# TSOC_GROVEY_FOUR.net
KiCad netlist of a schematic drawn in EAGLE
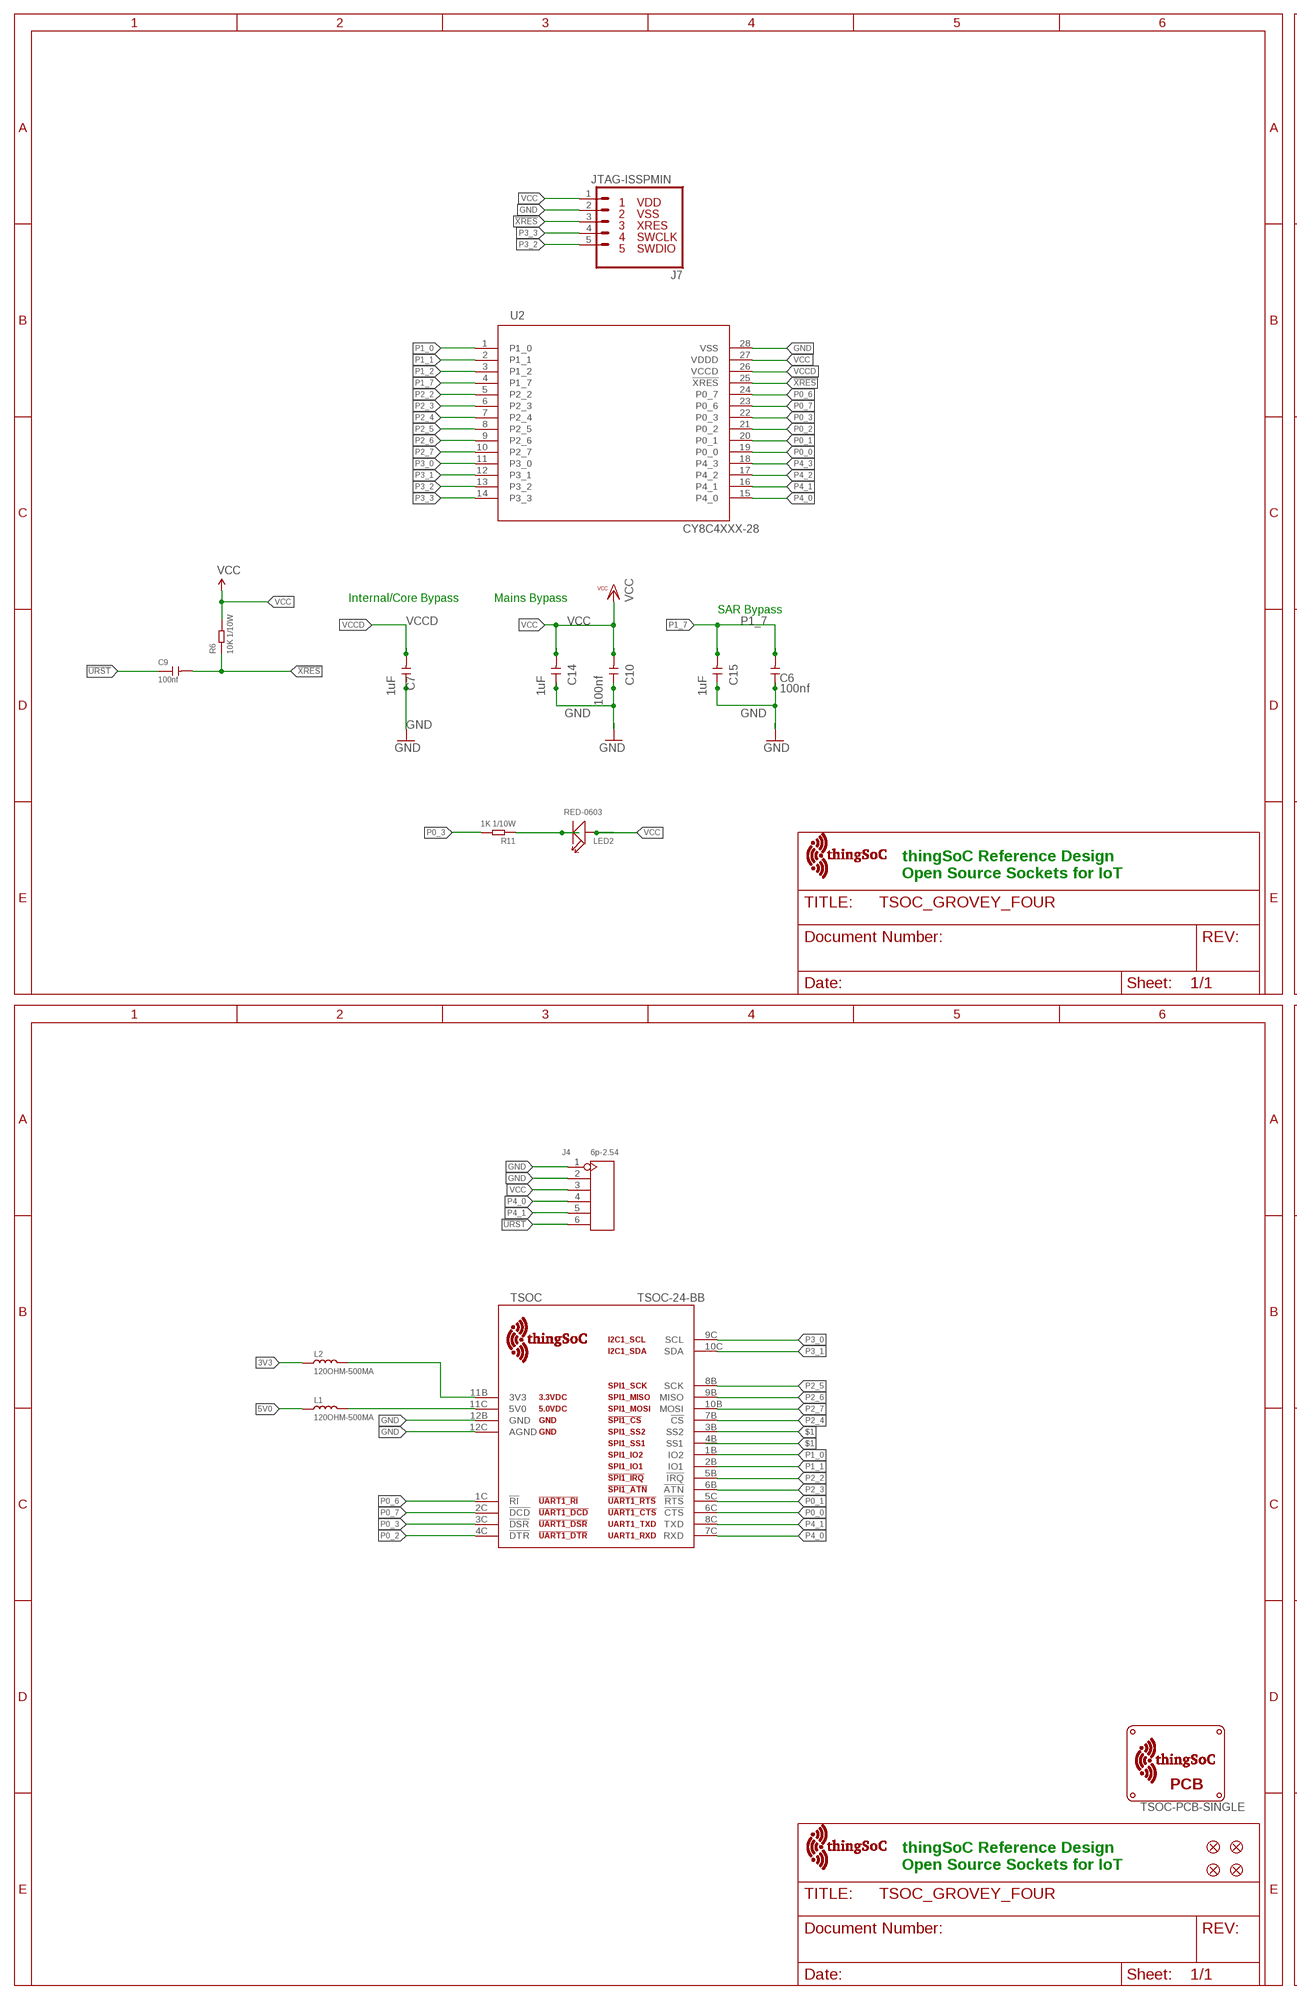
[diagram p0: schematic, sheet 1, part 1 of 2]
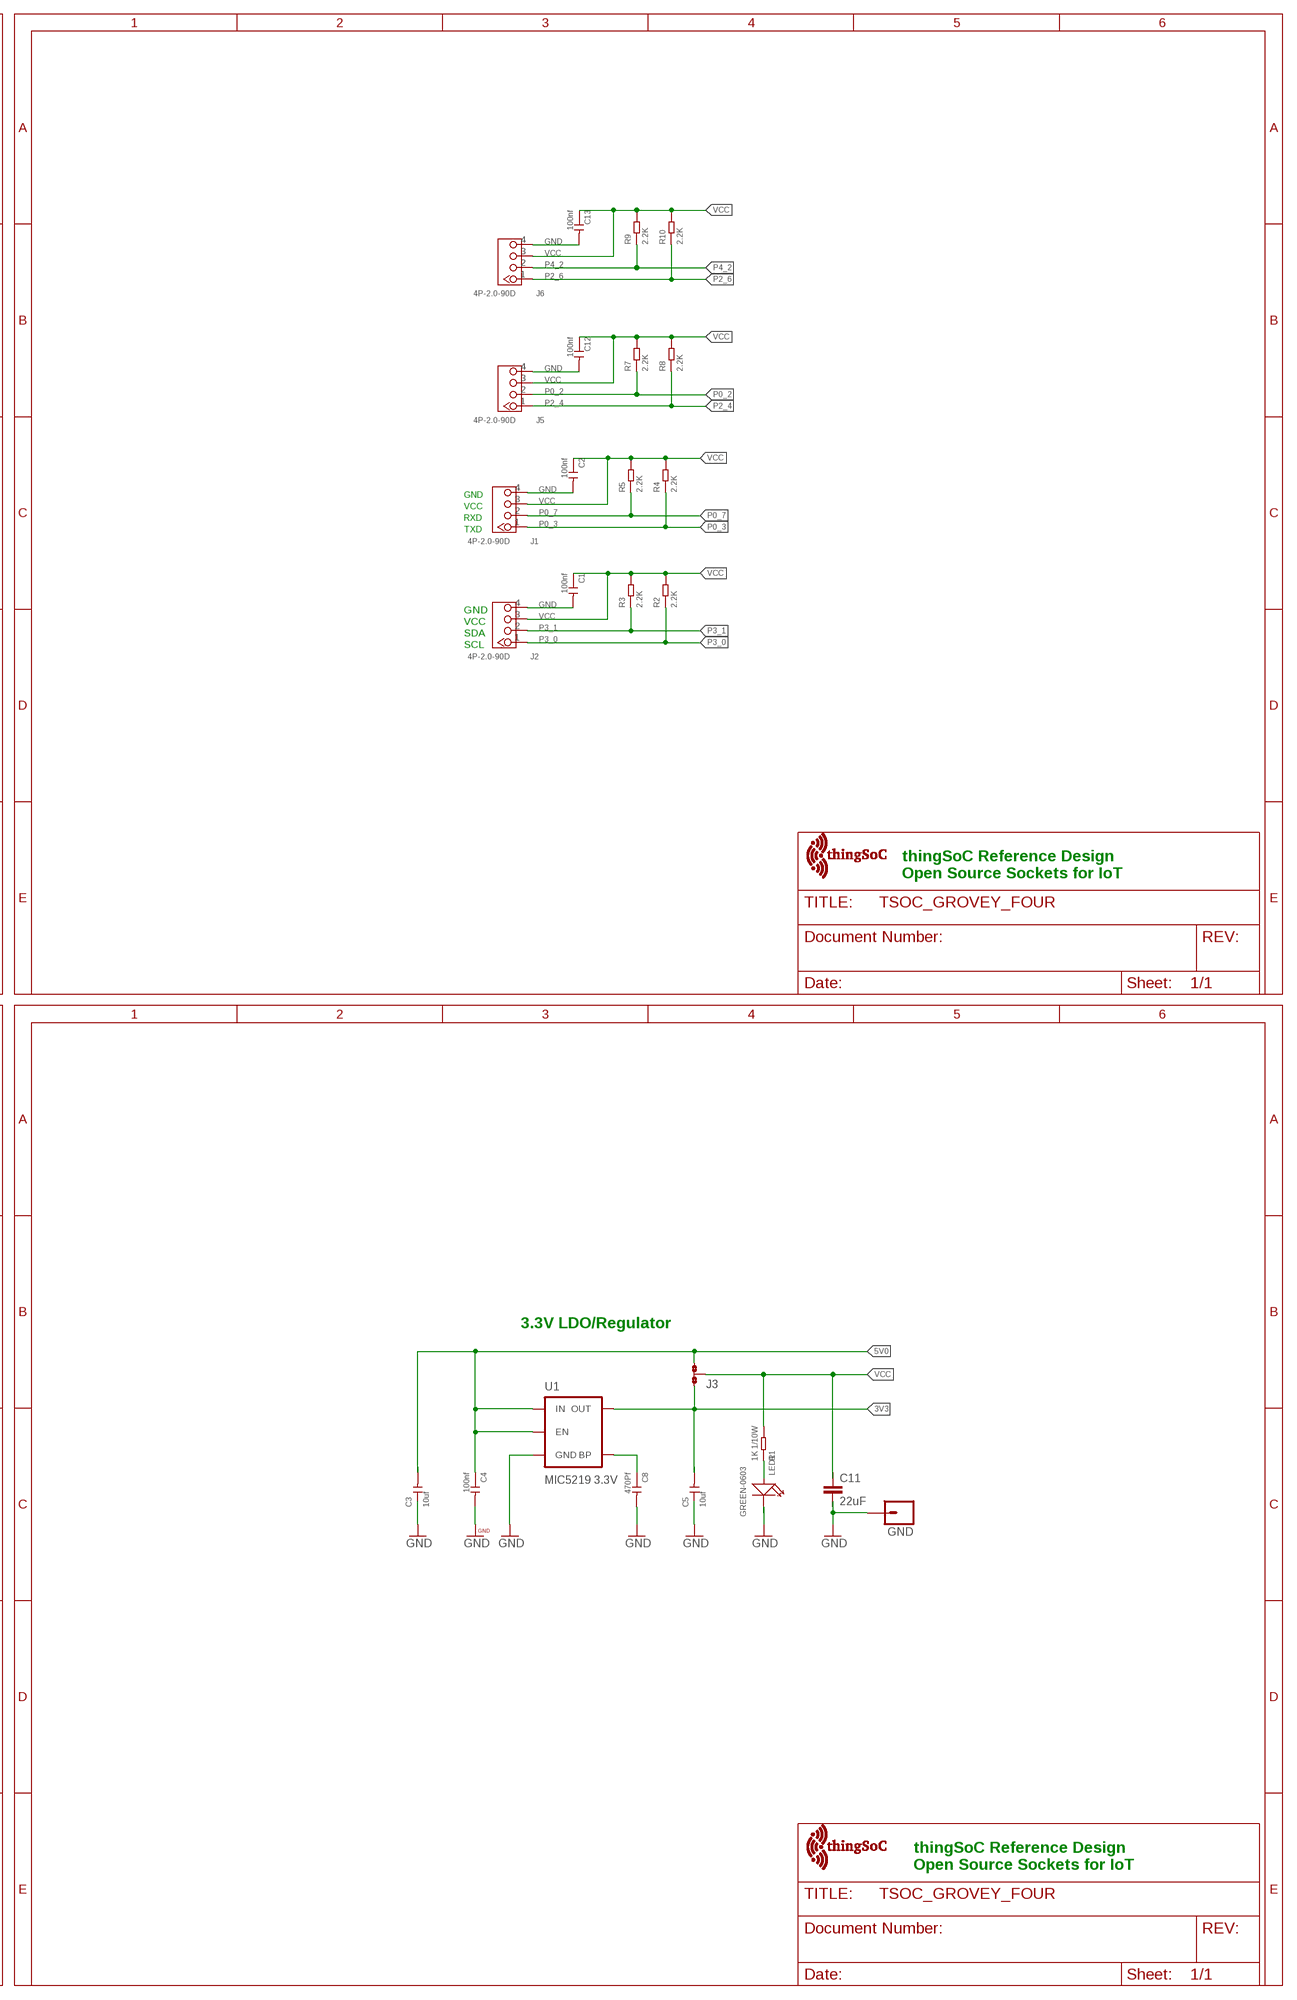
[diagram p1: schematic, sheet 1, part 2 of 2]

(export (version "E")
  (design (tool "Eeschema 10.0.6"))
  (components
    (comp (ref "$$U$1")
      (value "TSOC-PCB-SINGLE")
      (footprint "eagle-import:TSOC-BB-BRD-DIM")
      (libsource (lib "eagle-import") (part "TSOC-PCB-SINGLE"))
    )
    (comp (ref "C1")
      (value "100nf")
      (footprint "eagle-import:C0603")
      (fields (field (name "MPN") "CC0603KRX7R9BB104"))
      (libsource (lib "eagle-import") (part "CERAMIC-100NF-50V-10%-X7R(0603)"))
    )
    (comp (ref "C2")
      (value "100nf")
      (footprint "eagle-import:C0603")
      (fields (field (name "MPN") "CC0603KRX7R9BB104"))
      (libsource (lib "eagle-import") (part "CERAMIC-100NF-50V-10%-X7R(0603)"))
    )
    (comp (ref "C3")
      (value "10uf")
      (footprint "eagle-import:C0603")
      (fields (field (name "MPN") "CC0603KRX5R6BB106"))
      (libsource (lib "eagle-import") (part "CERAMIC-10UF-10V-10%-X5R(0603)"))
    )
    (comp (ref "C4")
      (value "100nf")
      (footprint "eagle-import:C0603")
      (fields (field (name "MPN") "CC0603KRX7R9BB104"))
      (libsource (lib "eagle-import") (part "CERAMIC-100NF-50V-10%-X7R(0603)"))
    )
    (comp (ref "C5")
      (value "10uf")
      (footprint "eagle-import:C0603")
      (fields (field (name "MPN") "CC0603KRX5R6BB106"))
      (libsource (lib "eagle-import") (part "CERAMIC-10UF-10V-10%-X5R(0603)"))
    )
    (comp (ref "C6")
      (value "100nf")
      (footprint "eagle-import:C0603")
      (fields (field (name "MPN") "CC0603KRX7R9BB104"))
      (libsource (lib "eagle-import") (part "CERAMIC-100NF-50V-10%-X7R(0603)"))
    )
    (comp (ref "C7")
      (value "1uF")
      (footprint "eagle-import:C0603")
      (fields (field (name "MPN") "CC0603KRX7R9BB104"))
      (libsource (lib "eagle-import") (part "CERAMIC-100NF-50V-10%-X7R(0603)"))
    )
    (comp (ref "C8")
      (value "470Pf")
      (footprint "eagle-import:C0603")
      (fields (field (name "MPN") "CC0603KRX7R9BB104"))
      (libsource (lib "eagle-import") (part "CERAMIC-100NF-50V-10%-X7R(0603)"))
    )
    (comp (ref "C9")
      (value "100nf")
      (footprint "eagle-import:C0603")
      (fields (field (name "MPN") "CC0603KRX7R9BB104"))
      (libsource (lib "eagle-import") (part "CERAMIC-100NF-50V-10%-X7R(0603)"))
    )
    (comp (ref "C10")
      (value "100nf")
      (footprint "eagle-import:C0603")
      (fields (field (name "MPN") "CC0603KRX7R9BB104"))
      (libsource (lib "eagle-import") (part "CERAMIC-100NF-50V-10%-X7R(0603)"))
    )
    (comp (ref "C11")
      (value "22uF")
      (footprint "eagle-import:EIA-1206")
      (libsource (lib "eagle-import") (part "CAP-1206"))
    )
    (comp (ref "C12")
      (value "100nf")
      (footprint "eagle-import:C0603")
      (fields (field (name "MPN") "CC0603KRX7R9BB104"))
      (libsource (lib "eagle-import") (part "CERAMIC-100NF-50V-10%-X7R(0603)"))
    )
    (comp (ref "C13")
      (value "100nf")
      (footprint "eagle-import:C0603")
      (fields (field (name "MPN") "CC0603KRX7R9BB104"))
      (libsource (lib "eagle-import") (part "CERAMIC-100NF-50V-10%-X7R(0603)"))
    )
    (comp (ref "C14")
      (value "1uF")
      (footprint "eagle-import:C0603")
      (fields (field (name "MPN") "CC0603KRX7R9BB104"))
      (libsource (lib "eagle-import") (part "CERAMIC-100NF-50V-10%-X7R(0603)"))
    )
    (comp (ref "C15")
      (value "1uF")
      (footprint "eagle-import:C0603")
      (fields (field (name "MPN") "CC0603KRX7R9BB104"))
      (libsource (lib "eagle-import") (part "CERAMIC-100NF-50V-10%-X7R(0603)"))
    )
    (comp (ref "FID1")
      (value "FIDUCIALUFIDUCIAL")
      (footprint "eagle-import:MICRO-FIDUCIAL")
      (libsource (lib "eagle-import") (part "FIDUCIALUFIDUCIAL"))
    )
    (comp (ref "FID2")
      (value "FIDUCIALUFIDUCIAL")
      (footprint "eagle-import:MICRO-FIDUCIAL")
      (libsource (lib "eagle-import") (part "FIDUCIALUFIDUCIAL"))
    )
    (comp (ref "FID3")
      (value "FIDUCIALUFIDUCIAL")
      (footprint "eagle-import:MICRO-FIDUCIAL")
      (libsource (lib "eagle-import") (part "FIDUCIALUFIDUCIAL"))
    )
    (comp (ref "FID4")
      (value "FIDUCIALUFIDUCIAL")
      (footprint "eagle-import:MICRO-FIDUCIAL")
      (libsource (lib "eagle-import") (part "FIDUCIALUFIDUCIAL"))
    )
    (comp (ref "GND")
      (value "M01PTH")
      (footprint "eagle-import:1X01")
      (libsource (lib "eagle-import") (part "M01PTH"))
    )
    (comp (ref "J1")
      (value "4P-2.0-90D")
      (footprint "eagle-import:HW4-2.0-90D")
      (libsource (lib "eagle-import") (part "GROVE-CONNECTOR-DIP-90D(4P-2.0)"))
    )
    (comp (ref "J2")
      (value "4P-2.0-90D")
      (footprint "eagle-import:HW4-2.0-90D")
      (libsource (lib "eagle-import") (part "GROVE-CONNECTOR-DIP-90D(4P-2.0)"))
    )
    (comp (ref "J3")
      (value "NO")
      (footprint "eagle-import:JMP-3-NO-PTH-2.54")
      (libsource (lib "eagle-import") (part "JMP-3-NO-PTH"))
    )
    (comp (ref "J4")
      (value "6p-2.54")
      (footprint "eagle-import:H6-2.54")
      (fields (field (name "MPN") "P125-1106A1BS116A1"))
      (libsource (lib "eagle-import") (part "DIP-BLACK-MALE-HEADER(6P-2.54)"))
    )
    (comp (ref "J5")
      (value "4P-2.0-90D")
      (footprint "eagle-import:HW4-2.0-90D")
      (libsource (lib "eagle-import") (part "GROVE-CONNECTOR-DIP-90D(4P-2.0)"))
    )
    (comp (ref "J6")
      (value "4P-2.0-90D")
      (footprint "eagle-import:HW4-2.0-90D")
      (libsource (lib "eagle-import") (part "GROVE-CONNECTOR-DIP-90D(4P-2.0)"))
    )
    (comp (ref "J7")
      (value "JTAG-ISSPMIN")
      (footprint "eagle-import:PSOC_JTAG_MINSILK")
      (libsource (lib "eagle-import") (part "JTAG-ISSPMIN"))
    )
    (comp (ref "L1")
      (value "120OHM-500MA")
      (footprint "eagle-import:L0603")
      (fields (field (name "MPN") "BLM18AG121SN1D"))
      (libsource (lib "eagle-import") (part "SMD-FERRITE-CHIP-120-OHM-500MA(0603)"))
    )
    (comp (ref "L2")
      (value "120OHM-500MA")
      (footprint "eagle-import:L0603")
      (fields (field (name "MPN") "BLM18AG121SN1D"))
      (libsource (lib "eagle-import") (part "SMD-FERRITE-CHIP-120-OHM-500MA(0603)"))
    )
    (comp (ref "LED1")
      (value "GREEN-0603")
      (footprint "eagle-import:LED-0603")
      (fields (field (name "MPN") "19-217-G7C-AN1P2-3T"))
      (libsource (lib "eagle-import") (part "SMD-LED-CLEAR-GREEN(0603)"))
    )
    (comp (ref "LED2")
      (value "RED-0603")
      (footprint "eagle-import:LED-0603")
      (fields (field (name "MPN") "19-217-G7C-AN1P2-3T"))
      (libsource (lib "eagle-import") (part "SMD-LED-CLEAR-GREEN(0603)"))
    )
    (comp (ref "R1")
      (value "1K 1/10W")
      (footprint "eagle-import:R0603")
      (fields (field (name "MPN") "RC0603JR-071KL"))
      (libsource (lib "eagle-import") (part "SMD-RES-1K-5%-1/10W(0603)"))
    )
    (comp (ref "R2")
      (value "2.2K")
      (footprint "eagle-import:R0603")
      (fields (field (name "MPN") "RC0603JR-072K2L"))
      (libsource (lib "eagle-import") (part "SMD-RES-2.2K-5%-1/10W(0603)"))
    )
    (comp (ref "R3")
      (value "2.2K")
      (footprint "eagle-import:R0603")
      (fields (field (name "MPN") "RC0603JR-072K2L"))
      (libsource (lib "eagle-import") (part "SMD-RES-2.2K-5%-1/10W(0603)"))
    )
    (comp (ref "R4")
      (value "2.2K")
      (footprint "eagle-import:R0603")
      (fields (field (name "MPN") "RC0603JR-072K2L"))
      (libsource (lib "eagle-import") (part "SMD-RES-2.2K-5%-1/10W(0603)"))
    )
    (comp (ref "R5")
      (value "2.2K")
      (footprint "eagle-import:R0603")
      (fields (field (name "MPN") "RC0603JR-072K2L"))
      (libsource (lib "eagle-import") (part "SMD-RES-2.2K-5%-1/10W(0603)"))
    )
    (comp (ref "R6")
      (value "10K 1/10W")
      (footprint "eagle-import:R0603")
      (fields (field (name "MPN") "RC0603JR-0710KL"))
      (libsource (lib "eagle-import") (part "SMD-RES-10K-5%-1/10W(0603)"))
    )
    (comp (ref "R7")
      (value "2.2K")
      (footprint "eagle-import:R0603")
      (fields (field (name "MPN") "RC0603JR-072K2L"))
      (libsource (lib "eagle-import") (part "SMD-RES-2.2K-5%-1/10W(0603)"))
    )
    (comp (ref "R8")
      (value "2.2K")
      (footprint "eagle-import:R0603")
      (fields (field (name "MPN") "RC0603JR-072K2L"))
      (libsource (lib "eagle-import") (part "SMD-RES-2.2K-5%-1/10W(0603)"))
    )
    (comp (ref "R9")
      (value "2.2K")
      (footprint "eagle-import:R0603")
      (fields (field (name "MPN") "RC0603JR-072K2L"))
      (libsource (lib "eagle-import") (part "SMD-RES-2.2K-5%-1/10W(0603)"))
    )
    (comp (ref "R10")
      (value "2.2K")
      (footprint "eagle-import:R0603")
      (fields (field (name "MPN") "RC0603JR-072K2L"))
      (libsource (lib "eagle-import") (part "SMD-RES-2.2K-5%-1/10W(0603)"))
    )
    (comp (ref "R11")
      (value "1K 1/10W")
      (footprint "eagle-import:R0603")
      (fields (field (name "MPN") "RC0603JR-071KL"))
      (libsource (lib "eagle-import") (part "SMD-RES-1K-5%-1/10W(0603)"))
    )
    (comp (ref "TSOC")
      (value "TSOC-24-BB")
      (footprint "eagle-import:TSOC-BB-S24")
      (libsource (lib "eagle-import") (part "TSOC-24-BB"))
    )
    (comp (ref "U$1")
      (value "TSOC-LOGO-SMALL")
      (footprint "eagle-import:TSOC-LOGO-SML")
      (libsource (lib "eagle-import") (part "TSOC-LOGO-SMALL"))
    )
    (comp (ref "U$101")
      (value "TSOC-LOGO-SMALL")
      (footprint "eagle-import:TSOC-LOGO-SML")
      (libsource (lib "eagle-import") (part "TSOC-LOGO-SMALL"))
    )
    (comp (ref "U$102")
      (value "TSOC-LOGO-LRG")
      (footprint "eagle-import:TSOC-LOGO-LRG")
      (libsource (lib "eagle-import") (part "TSOC-LOGO-LRG"))
    )
    (comp (ref "U$103")
      (value "TSOC-LOGO-SMALL")
      (footprint "eagle-import:TSOC-LOGO-SML")
      (libsource (lib "eagle-import") (part "TSOC-LOGO-SMALL"))
    )
    (comp (ref "U1")
      (value "MIC5219 3.3V")
      (footprint "eagle-import:SOT23-5")
      (libsource (lib "eagle-import") (part "V_REG_MIC52193.3V"))
    )
    (comp (ref "U2")
      (value "CY8C4XXX-28")
      (footprint "eagle-import:SSOP28")
      (libsource (lib "eagle-import") (part "CY8C4XXX-28"))
    )
  )
  (nets
    (net (code "1") (name "$1") (class "Default")
      (node (ref "TSOC") (pin "3B") (pinfunction "SS2_3B") (pintype "bidirectional"))
      (node (ref "TSOC") (pin "4B") (pinfunction "SS1_4B") (pintype "bidirectional"))
    )
    (net (code "2") (name "/~{URST}") (class "Default")
      (node (ref "C9") (pin "1") (pinfunction "1_1") (pintype "passive"))
      (node (ref "J4") (pin "6") (pinfunction "6_6") (pintype "bidirectional"))
    )
    (net (code "3") (name "/~{XRES}") (class "Default")
      (node (ref "C9") (pin "2") (pinfunction "2_2") (pintype "passive"))
      (node (ref "J7") (pin "3") (pinfunction "3_3") (pintype "passive"))
      (node (ref "R6") (pin "1") (pinfunction "1_1") (pintype "passive"))
      (node (ref "U2") (pin "25") (pinfunction "~{XRES}_25") (pintype "bidirectional"))
    )
    (net (code "4") (name "3V3") (class "Default")
      (node (ref "C5") (pin "2") (pinfunction "2_2") (pintype "passive"))
      (node (ref "J3") (pin "1") (pinfunction "1_1") (pintype "passive"))
      (node (ref "L2") (pin "1") (pinfunction "1_1") (pintype "passive"))
      (node (ref "U1") (pin "5") (pinfunction "OUT_5") (pintype "passive"))
    )
    (net (code "5") (name "5V0") (class "Default")
      (node (ref "C3") (pin "2") (pinfunction "2_2") (pintype "passive"))
      (node (ref "C4") (pin "1") (pinfunction "1_1") (pintype "passive"))
      (node (ref "J3") (pin "3") (pinfunction "3_3") (pintype "passive"))
      (node (ref "L1") (pin "1") (pinfunction "1_1") (pintype "passive"))
      (node (ref "U1") (pin "1") (pinfunction "IN_1") (pintype "input"))
      (node (ref "U1") (pin "3") (pinfunction "EN_3") (pintype "input"))
    )
    (net (code "6") (name "GND") (class "Default")
      (node (ref "C1") (pin "2") (pinfunction "2_2") (pintype "passive"))
      (node (ref "C10") (pin "1") (pinfunction "1_1") (pintype "passive"))
      (node (ref "C11") (pin "2") (pinfunction "2_2") (pintype "passive"))
      (node (ref "C12") (pin "2") (pinfunction "2_2") (pintype "passive"))
      (node (ref "C13") (pin "2") (pinfunction "2_2") (pintype "passive"))
      (node (ref "C14") (pin "1") (pinfunction "1_1") (pintype "passive"))
      (node (ref "C15") (pin "1") (pinfunction "1_1") (pintype "passive"))
      (node (ref "C2") (pin "2") (pinfunction "2_2") (pintype "passive"))
      (node (ref "C3") (pin "1") (pinfunction "1_1") (pintype "passive"))
      (node (ref "C4") (pin "2") (pinfunction "2_2") (pintype "passive"))
      (node (ref "C5") (pin "1") (pinfunction "1_1") (pintype "passive"))
      (node (ref "C6") (pin "1") (pinfunction "1_1") (pintype "passive"))
      (node (ref "C7") (pin "1") (pinfunction "1_1") (pintype "passive"))
      (node (ref "C8") (pin "2") (pinfunction "2_2") (pintype "passive"))
      (node (ref "GND") (pin "1") (pinfunction "1_1") (pintype "passive"))
      (node (ref "J1") (pin "4") (pinfunction "4_4") (pintype "bidirectional"))
      (node (ref "J2") (pin "4") (pinfunction "4_4") (pintype "bidirectional"))
      (node (ref "J4") (pin "1") (pinfunction "1_1") (pintype "bidirectional"))
      (node (ref "J4") (pin "2") (pinfunction "2_2") (pintype "bidirectional"))
      (node (ref "J5") (pin "4") (pinfunction "4_4") (pintype "bidirectional"))
      (node (ref "J6") (pin "4") (pinfunction "4_4") (pintype "bidirectional"))
      (node (ref "J7") (pin "2") (pinfunction "2_2") (pintype "passive"))
      (node (ref "LED1") (pin "-") (pinfunction "-_-") (pintype "passive"))
      (node (ref "TSOC") (pin "12B") (pinfunction "GND_12B") (pintype "bidirectional"))
      (node (ref "TSOC") (pin "12C") (pinfunction "AGND_12C") (pintype "bidirectional"))
      (node (ref "U1") (pin "2") (pinfunction "GND_2") (pintype "input"))
      (node (ref "U2") (pin "28") (pinfunction "VSS_28") (pintype "bidirectional"))
    )
    (net (code "7") (name "Net-(LED1-Pad+)") (class "Default")
      (node (ref "LED1") (pin "+") (pinfunction "+_+") (pintype "passive"))
      (node (ref "R1") (pin "1") (pinfunction "1_1") (pintype "passive"))
    )
    (net (code "8") (name "Net-(LED2-Pad-)") (class "Default")
      (node (ref "LED2") (pin "-") (pinfunction "-_-") (pintype "passive"))
      (node (ref "R11") (pin "1") (pinfunction "1_1") (pintype "passive"))
    )
    (net (code "9") (name "Net-(TSOC-3V3)") (class "Default")
      (node (ref "L2") (pin "2") (pinfunction "2_2") (pintype "passive"))
      (node (ref "TSOC") (pin "11B") (pinfunction "3V3_11B") (pintype "bidirectional"))
    )
    (net (code "10") (name "Net-(TSOC-5V0)") (class "Default")
      (node (ref "L1") (pin "2") (pinfunction "2_2") (pintype "passive"))
      (node (ref "TSOC") (pin "11C") (pinfunction "5V0_11C") (pintype "bidirectional"))
    )
    (net (code "11") (name "Net-(U1-BP)") (class "Default")
      (node (ref "C8") (pin "1") (pinfunction "1_1") (pintype "passive"))
      (node (ref "U1") (pin "4") (pinfunction "BP_4") (pintype "input"))
    )
    (net (code "12") (name "P0_0") (class "Default")
      (node (ref "TSOC") (pin "6C") (pinfunction "~{CTS}_6C") (pintype "bidirectional"))
      (node (ref "U2") (pin "19") (pinfunction "P0_0_19") (pintype "bidirectional"))
    )
    (net (code "13") (name "P0_1") (class "Default")
      (node (ref "TSOC") (pin "5C") (pinfunction "~{RTS}_5C") (pintype "bidirectional"))
      (node (ref "U2") (pin "20") (pinfunction "P0_1_20") (pintype "bidirectional"))
    )
    (net (code "14") (name "P0_2") (class "Default")
      (node (ref "J5") (pin "2") (pinfunction "2_2") (pintype "bidirectional"))
      (node (ref "R7") (pin "1") (pinfunction "1_1") (pintype "passive"))
      (node (ref "TSOC") (pin "4C") (pinfunction "~{DTR}_4C") (pintype "bidirectional"))
      (node (ref "U2") (pin "21") (pinfunction "P0_2_21") (pintype "bidirectional"))
    )
    (net (code "15") (name "P0_3") (class "Default")
      (node (ref "J1") (pin "1") (pinfunction "1_1") (pintype "bidirectional"))
      (node (ref "R11") (pin "2") (pinfunction "2_2") (pintype "passive"))
      (node (ref "R4") (pin "1") (pinfunction "1_1") (pintype "passive"))
      (node (ref "TSOC") (pin "3C") (pinfunction "~{DSR}_3C") (pintype "bidirectional"))
      (node (ref "U2") (pin "22") (pinfunction "P0_3_22") (pintype "bidirectional"))
    )
    (net (code "16") (name "P0_6") (class "Default")
      (node (ref "TSOC") (pin "1C") (pinfunction "~{RI}_1C") (pintype "bidirectional"))
      (node (ref "U2") (pin "24") (pinfunction "P0_7_24") (pintype "bidirectional"))
    )
    (net (code "17") (name "P0_7") (class "Default")
      (node (ref "J1") (pin "2") (pinfunction "2_2") (pintype "bidirectional"))
      (node (ref "R5") (pin "1") (pinfunction "1_1") (pintype "passive"))
      (node (ref "TSOC") (pin "2C") (pinfunction "~{DCD}_2C") (pintype "bidirectional"))
      (node (ref "U2") (pin "23") (pinfunction "P0_6_23") (pintype "bidirectional"))
    )
    (net (code "18") (name "P1_0") (class "Default")
      (node (ref "TSOC") (pin "1B") (pinfunction "IO2_1B") (pintype "bidirectional"))
      (node (ref "U2") (pin "1") (pinfunction "P1_0_1") (pintype "bidirectional"))
    )
    (net (code "19") (name "P1_1") (class "Default")
      (node (ref "TSOC") (pin "2B") (pinfunction "IO1_2B") (pintype "bidirectional"))
      (node (ref "U2") (pin "2") (pinfunction "P1_1_2") (pintype "bidirectional"))
    )
    (net (code "20") (name "P1_2") (class "Default")
      (node (ref "U2") (pin "3") (pinfunction "P1_2_3") (pintype "bidirectional"))
    )
    (net (code "21") (name "P1_7") (class "Default")
      (node (ref "C15") (pin "2") (pinfunction "2_2") (pintype "passive"))
      (node (ref "C6") (pin "2") (pinfunction "2_2") (pintype "passive"))
      (node (ref "U2") (pin "4") (pinfunction "P1_7_4") (pintype "bidirectional"))
    )
    (net (code "22") (name "P2_2") (class "Default")
      (node (ref "TSOC") (pin "5B") (pinfunction "~{IRQ}_5B") (pintype "bidirectional"))
      (node (ref "U2") (pin "5") (pinfunction "P2_2_5") (pintype "bidirectional"))
    )
    (net (code "23") (name "P2_3") (class "Default")
      (node (ref "TSOC") (pin "6B") (pinfunction "~{ATN}_6B") (pintype "bidirectional"))
      (node (ref "U2") (pin "6") (pinfunction "P2_3_6") (pintype "bidirectional"))
    )
    (net (code "24") (name "P2_4") (class "Default")
      (node (ref "J5") (pin "1") (pinfunction "1_1") (pintype "bidirectional"))
      (node (ref "R8") (pin "1") (pinfunction "1_1") (pintype "passive"))
      (node (ref "TSOC") (pin "7B") (pinfunction "~{CS}_7B") (pintype "bidirectional"))
      (node (ref "U2") (pin "7") (pinfunction "P2_4_7") (pintype "bidirectional"))
    )
    (net (code "25") (name "P2_5") (class "Default")
      (node (ref "TSOC") (pin "8B") (pinfunction "SCK_8B") (pintype "bidirectional"))
      (node (ref "U2") (pin "8") (pinfunction "P2_5_8") (pintype "bidirectional"))
    )
    (net (code "26") (name "P2_6") (class "Default")
      (node (ref "J6") (pin "1") (pinfunction "1_1") (pintype "bidirectional"))
      (node (ref "R10") (pin "1") (pinfunction "1_1") (pintype "passive"))
      (node (ref "TSOC") (pin "9B") (pinfunction "MISO_9B") (pintype "bidirectional"))
      (node (ref "U2") (pin "9") (pinfunction "P2_6_9") (pintype "bidirectional"))
    )
    (net (code "27") (name "P2_7") (class "Default")
      (node (ref "TSOC") (pin "10B") (pinfunction "MOSI_10B") (pintype "bidirectional"))
      (node (ref "U2") (pin "10") (pinfunction "P2_7_10") (pintype "bidirectional"))
    )
    (net (code "28") (name "P3_0") (class "Default")
      (node (ref "J2") (pin "1") (pinfunction "1_1") (pintype "bidirectional"))
      (node (ref "R2") (pin "1") (pinfunction "1_1") (pintype "passive"))
      (node (ref "TSOC") (pin "9C") (pinfunction "SCL_9C") (pintype "bidirectional"))
      (node (ref "U2") (pin "11") (pinfunction "P3_0_11") (pintype "bidirectional"))
    )
    (net (code "29") (name "P3_1") (class "Default")
      (node (ref "J2") (pin "2") (pinfunction "2_2") (pintype "bidirectional"))
      (node (ref "R3") (pin "1") (pinfunction "1_1") (pintype "passive"))
      (node (ref "TSOC") (pin "10C") (pinfunction "SDA_10C") (pintype "bidirectional"))
      (node (ref "U2") (pin "12") (pinfunction "P3_1_12") (pintype "bidirectional"))
    )
    (net (code "30") (name "P3_2") (class "Default")
      (node (ref "J7") (pin "5") (pinfunction "5_5") (pintype "passive"))
      (node (ref "U2") (pin "13") (pinfunction "P3_2_13") (pintype "bidirectional"))
    )
    (net (code "31") (name "P3_3") (class "Default")
      (node (ref "J7") (pin "4") (pinfunction "4_4") (pintype "passive"))
      (node (ref "U2") (pin "14") (pinfunction "P3_3_14") (pintype "bidirectional"))
    )
    (net (code "32") (name "P4_0") (class "Default")
      (node (ref "J4") (pin "4") (pinfunction "4_4") (pintype "bidirectional"))
      (node (ref "TSOC") (pin "7C") (pinfunction "RXD_7C") (pintype "bidirectional"))
      (node (ref "U2") (pin "15") (pinfunction "P4_0_15") (pintype "bidirectional"))
    )
    (net (code "33") (name "P4_1") (class "Default")
      (node (ref "J4") (pin "5") (pinfunction "5_5") (pintype "bidirectional"))
      (node (ref "TSOC") (pin "8C") (pinfunction "TXD_8C") (pintype "bidirectional"))
      (node (ref "U2") (pin "16") (pinfunction "P4_1_16") (pintype "bidirectional"))
    )
    (net (code "34") (name "P4_2") (class "Default")
      (node (ref "J6") (pin "2") (pinfunction "2_2") (pintype "bidirectional"))
      (node (ref "R9") (pin "1") (pinfunction "1_1") (pintype "passive"))
      (node (ref "U2") (pin "17") (pinfunction "P4_2_17") (pintype "bidirectional"))
    )
    (net (code "35") (name "P4_3") (class "Default")
      (node (ref "U2") (pin "18") (pinfunction "P4_3_18") (pintype "bidirectional"))
    )
    (net (code "36") (name "VCC") (class "Default")
      (node (ref "C1") (pin "1") (pinfunction "1_1") (pintype "passive"))
      (node (ref "C10") (pin "2") (pinfunction "2_2") (pintype "passive"))
      (node (ref "C11") (pin "1") (pinfunction "1_1") (pintype "passive"))
      (node (ref "C12") (pin "1") (pinfunction "1_1") (pintype "passive"))
      (node (ref "C13") (pin "1") (pinfunction "1_1") (pintype "passive"))
      (node (ref "C14") (pin "2") (pinfunction "2_2") (pintype "passive"))
      (node (ref "C2") (pin "1") (pinfunction "1_1") (pintype "passive"))
      (node (ref "J1") (pin "3") (pinfunction "3_3") (pintype "bidirectional"))
      (node (ref "J2") (pin "3") (pinfunction "3_3") (pintype "bidirectional"))
      (node (ref "J3") (pin "2") (pinfunction "2_2") (pintype "passive"))
      (node (ref "J4") (pin "3") (pinfunction "3_3") (pintype "bidirectional"))
      (node (ref "J5") (pin "3") (pinfunction "3_3") (pintype "bidirectional"))
      (node (ref "J6") (pin "3") (pinfunction "3_3") (pintype "bidirectional"))
      (node (ref "J7") (pin "1") (pinfunction "1_1") (pintype "passive"))
      (node (ref "LED2") (pin "+") (pinfunction "+_+") (pintype "passive"))
      (node (ref "R1") (pin "2") (pinfunction "2_2") (pintype "passive"))
      (node (ref "R10") (pin "2") (pinfunction "2_2") (pintype "passive"))
      (node (ref "R2") (pin "2") (pinfunction "2_2") (pintype "passive"))
      (node (ref "R3") (pin "2") (pinfunction "2_2") (pintype "passive"))
      (node (ref "R4") (pin "2") (pinfunction "2_2") (pintype "passive"))
      (node (ref "R5") (pin "2") (pinfunction "2_2") (pintype "passive"))
      (node (ref "R6") (pin "2") (pinfunction "2_2") (pintype "passive"))
      (node (ref "R7") (pin "2") (pinfunction "2_2") (pintype "passive"))
      (node (ref "R8") (pin "2") (pinfunction "2_2") (pintype "passive"))
      (node (ref "R9") (pin "2") (pinfunction "2_2") (pintype "passive"))
      (node (ref "U2") (pin "27") (pinfunction "VDDD_27") (pintype "bidirectional"))
    )
    (net (code "37") (name "VCCD") (class "Default")
      (node (ref "C7") (pin "2") (pinfunction "2_2") (pintype "passive"))
      (node (ref "U2") (pin "26") (pinfunction "VCCD_26") (pintype "bidirectional"))
    )
  )
)
